# NBIOT.net
KiCad netlist of a schematic drawn in Altium Designer
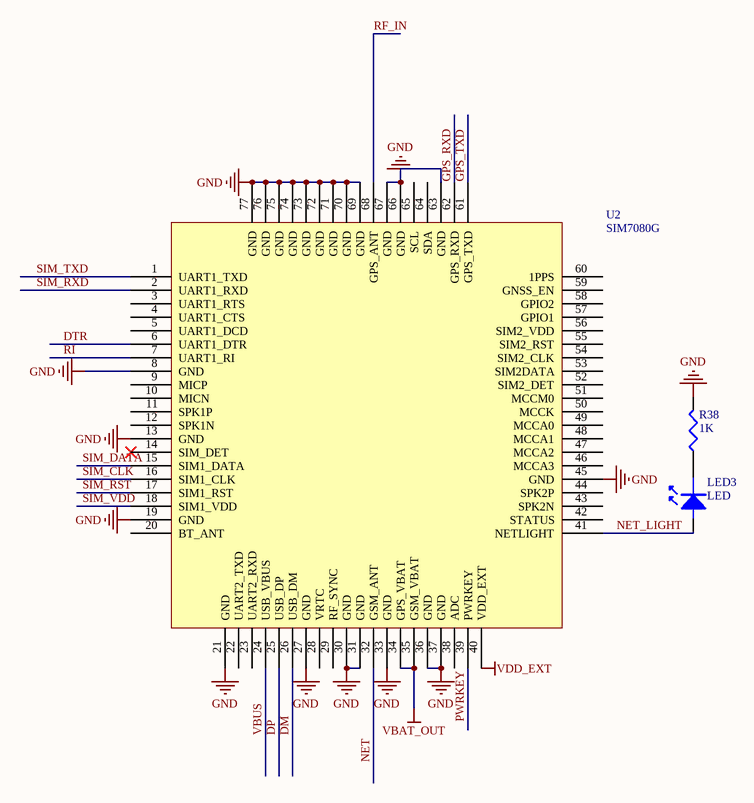
[diagram p0: NBIOT.SchDoc]

(export (version "E")
  (design (tool "Eeschema 10.0.6"))
  (components
    (comp (ref "LED3") (value "LED") (footprint "0603LED") (libsource (lib "我的元件库") (part "LED")))
    (comp (ref "R38")
      (value "1K")
      (footprint "0402R")
      (libsource (lib "ZWLIntegrated_Library") (part "RES1"))
    )
    (comp (ref "U2")
      (value "SIM7080G")
      (footprint "SIM868")
      (libsource (lib "stm32") (part "SIM868E/SIM868"))
    )
  )
  (nets
    (net (code "1") (name "/DM") (class "Default")
      (node (ref "U2") (pin "26") (pinfunction "USB_DM_26") (pintype "passive"))
    )
    (net (code "2") (name "/DP") (class "Default")
      (node (ref "U2") (pin "25") (pinfunction "USB_DP_25") (pintype "passive"))
    )
    (net (code "3") (name "/DTR") (class "Default")
      (node (ref "U2") (pin "6") (pinfunction "UART1_DTR_6") (pintype "passive"))
    )
    (net (code "4") (name "/GPS_RXD") (class "Default")
      (node (ref "U2") (pin "62") (pinfunction "GPS_RXD_62") (pintype "passive"))
    )
    (net (code "5") (name "/GPS_TXD") (class "Default")
      (node (ref "U2") (pin "61") (pinfunction "GPS_TXD_61") (pintype "passive"))
    )
    (net (code "6") (name "/NET") (class "Default")
      (node (ref "U2") (pin "32") (pinfunction "GSM_ANT_32") (pintype "passive"))
    )
    (net (code "7") (name "/NET_LIGHT") (class "Default")
      (node (ref "LED3") (pin "1") (pinfunction "1_1") (pintype "passive"))
      (node (ref "U2") (pin "41") (pinfunction "NETLIGHT_41") (pintype "passive"))
    )
    (net (code "8") (name "/PWRKEY") (class "Default")
      (node (ref "U2") (pin "39") (pinfunction "PWRKEY_39") (pintype "passive"))
    )
    (net (code "9") (name "/RF_IN") (class "Default")
      (node (ref "U2") (pin "68") (pinfunction "GPS_ANT_68") (pintype "passive"))
    )
    (net (code "10") (name "/RI") (class "Default")
      (node (ref "U2") (pin "7") (pinfunction "UART1_RI_7") (pintype "passive"))
    )
    (net (code "11") (name "/SIM_CLK") (class "Default")
      (node (ref "U2") (pin "16") (pinfunction "SIM1_CLK_16") (pintype "passive"))
    )
    (net (code "12") (name "/SIM_DATA") (class "Default")
      (node (ref "U2") (pin "15") (pinfunction "SIM1_DATA_15") (pintype "passive"))
    )
    (net (code "13") (name "/SIM_RST") (class "Default")
      (node (ref "U2") (pin "17") (pinfunction "SIM1_RST_17") (pintype "passive"))
    )
    (net (code "14") (name "/SIM_RXD") (class "Default")
      (node (ref "U2") (pin "2") (pinfunction "UART1_RXD_2") (pintype "passive"))
    )
    (net (code "15") (name "/SIM_TXD") (class "Default")
      (node (ref "U2") (pin "1") (pinfunction "UART1_TXD_1") (pintype "passive"))
    )
    (net (code "16") (name "/SIM_VDD") (class "Default")
      (node (ref "U2") (pin "18") (pinfunction "SIM1_VDD_18") (pintype "passive"))
    )
    (net (code "17") (name "/VBUS") (class "Default")
      (node (ref "U2") (pin "24") (pinfunction "USB_VBUS_24") (pintype "passive"))
    )
    (net (code "18") (name "GND") (class "Default")
      (node (ref "R38") (pin "2") (pinfunction "2_2") (pintype "passive"))
      (node (ref "U2") (pin "13") (pinfunction "GND_13") (pintype "passive"))
      (node (ref "U2") (pin "19") (pinfunction "GND_19") (pintype "passive"))
      (node (ref "U2") (pin "21") (pinfunction "GND_21") (pintype "passive"))
      (node (ref "U2") (pin "27") (pinfunction "GND_27") (pintype "passive"))
      (node (ref "U2") (pin "30") (pinfunction "GND_30") (pintype "passive"))
      (node (ref "U2") (pin "31") (pinfunction "GND_31") (pintype "passive"))
      (node (ref "U2") (pin "33") (pinfunction "GND_33") (pintype "passive"))
      (node (ref "U2") (pin "36") (pinfunction "GND_36") (pintype "passive"))
      (node (ref "U2") (pin "37") (pinfunction "GND_37") (pintype "passive"))
      (node (ref "U2") (pin "45") (pinfunction "GND_45") (pintype "passive"))
      (node (ref "U2") (pin "63") (pinfunction "GND_63") (pintype "passive"))
      (node (ref "U2") (pin "66") (pinfunction "GND_66") (pintype "passive"))
      (node (ref "U2") (pin "67") (pinfunction "GND_67") (pintype "passive"))
      (node (ref "U2") (pin "69") (pinfunction "GND_69") (pintype "passive"))
      (node (ref "U2") (pin "70") (pinfunction "GND_70") (pintype "passive"))
      (node (ref "U2") (pin "71") (pinfunction "GND_71") (pintype "passive"))
      (node (ref "U2") (pin "72") (pinfunction "GND_72") (pintype "passive"))
      (node (ref "U2") (pin "73") (pinfunction "GND_73") (pintype "passive"))
      (node (ref "U2") (pin "74") (pinfunction "GND_74") (pintype "passive"))
      (node (ref "U2") (pin "75") (pinfunction "GND_75") (pintype "passive"))
      (node (ref "U2") (pin "76") (pinfunction "GND_76") (pintype "passive"))
      (node (ref "U2") (pin "77") (pinfunction "GND_77") (pintype "passive"))
      (node (ref "U2") (pin "8") (pinfunction "GND_8") (pintype "passive"))
    )
    (net (code "19") (name "Net-(LED3-Pad2)") (class "Default")
      (node (ref "LED3") (pin "2") (pinfunction "2_2") (pintype "passive"))
      (node (ref "R38") (pin "1") (pinfunction "1_1") (pintype "passive"))
    )
    (net (code "20") (name "VBAT_OUT") (class "Default")
      (node (ref "U2") (pin "34") (pinfunction "GPS_VBAT_34") (pintype "passive"))
      (node (ref "U2") (pin "35") (pinfunction "GSM_VBAT_35") (pintype "passive"))
    )
    (net (code "21") (name "VDD_EXT") (class "Default")
      (node (ref "U2") (pin "40") (pinfunction "VDD_EXT_40") (pintype "passive"))
    )
    (net (code "22") (name "unconnected-(U2-1PPS-Pad60)") (class "Default")
      (node (ref "U2") (pin "60") (pinfunction "1PPS_60") (pintype "passive"))
    )
    (net (code "23") (name "unconnected-(U2-ADC-Pad38)") (class "Default")
      (node (ref "U2") (pin "38") (pinfunction "ADC_38") (pintype "passive"))
    )
    (net (code "24") (name "unconnected-(U2-BT_ANT-Pad20)") (class "Default")
      (node (ref "U2") (pin "20") (pinfunction "BT_ANT_20") (pintype "passive"))
    )
    (net (code "25") (name "unconnected-(U2-GNSS_EN-Pad59)") (class "Default")
      (node (ref "U2") (pin "59") (pinfunction "GNSS_EN_59") (pintype "passive"))
    )
    (net (code "26") (name "unconnected-(U2-GPIO1-Pad57)") (class "Default")
      (node (ref "U2") (pin "57") (pinfunction "GPIO1_57") (pintype "passive"))
    )
    (net (code "27") (name "unconnected-(U2-GPIO2-Pad58)") (class "Default")
      (node (ref "U2") (pin "58") (pinfunction "GPIO2_58") (pintype "passive"))
    )
    (net (code "28") (name "unconnected-(U2-MCCA0-Pad49)") (class "Default")
      (node (ref "U2") (pin "49") (pinfunction "MCCA0_49") (pintype "passive"))
    )
    (net (code "29") (name "unconnected-(U2-MCCA1-Pad48)") (class "Default")
      (node (ref "U2") (pin "48") (pinfunction "MCCA1_48") (pintype "passive"))
    )
    (net (code "30") (name "unconnected-(U2-MCCA2-Pad47)") (class "Default")
      (node (ref "U2") (pin "47") (pinfunction "MCCA2_47") (pintype "passive"))
    )
    (net (code "31") (name "unconnected-(U2-MCCA3-Pad46)") (class "Default")
      (node (ref "U2") (pin "46") (pinfunction "MCCA3_46") (pintype "passive"))
    )
    (net (code "32") (name "unconnected-(U2-MCCK-Pad50)") (class "Default")
      (node (ref "U2") (pin "50") (pinfunction "MCCK_50") (pintype "passive"))
    )
    (net (code "33") (name "unconnected-(U2-MCCM0-Pad51)") (class "Default")
      (node (ref "U2") (pin "51") (pinfunction "MCCM0_51") (pintype "passive"))
    )
    (net (code "34") (name "unconnected-(U2-MICN-Pad10)") (class "Default")
      (node (ref "U2") (pin "10") (pinfunction "MICN_10") (pintype "passive"))
    )
    (net (code "35") (name "unconnected-(U2-MICP-Pad9)") (class "Default")
      (node (ref "U2") (pin "9") (pinfunction "MICP_9") (pintype "passive"))
    )
    (net (code "36") (name "unconnected-(U2-RF_SYNC-Pad29)") (class "Default")
      (node (ref "U2") (pin "29") (pinfunction "RF_SYNC_29") (pintype "passive"))
    )
    (net (code "37") (name "unconnected-(U2-SCL-Pad65)") (class "Default")
      (node (ref "U2") (pin "65") (pinfunction "SCL_65") (pintype "passive"))
    )
    (net (code "38") (name "unconnected-(U2-SDA-Pad64)") (class "Default")
      (node (ref "U2") (pin "64") (pinfunction "SDA_64") (pintype "passive"))
    )
    (net (code "39") (name "unconnected-(U2-SIM2DATA-Pad53)") (class "Default")
      (node (ref "U2") (pin "53") (pinfunction "SIM2DATA_53") (pintype "passive"))
    )
    (net (code "40") (name "unconnected-(U2-SIM2_CLK-Pad54)") (class "Default")
      (node (ref "U2") (pin "54") (pinfunction "SIM2_CLK_54") (pintype "passive"))
    )
    (net (code "41") (name "unconnected-(U2-SIM2_DET-Pad52)") (class "Default")
      (node (ref "U2") (pin "52") (pinfunction "SIM2_DET_52") (pintype "passive"))
    )
    (net (code "42") (name "unconnected-(U2-SIM2_RST-Pad55)") (class "Default")
      (node (ref "U2") (pin "55") (pinfunction "SIM2_RST_55") (pintype "passive"))
    )
    (net (code "43") (name "unconnected-(U2-SIM2_VDD-Pad56)") (class "Default")
      (node (ref "U2") (pin "56") (pinfunction "SIM2_VDD_56") (pintype "passive"))
    )
    (net (code "44") (name "unconnected-(U2-SIM_DET-Pad14)") (class "Default")
      (node (ref "U2") (pin "14") (pinfunction "SIM_DET_14") (pintype "passive+no_connect"))
    )
    (net (code "45") (name "unconnected-(U2-SPK1N-Pad12)") (class "Default")
      (node (ref "U2") (pin "12") (pinfunction "SPK1N_12") (pintype "passive"))
    )
    (net (code "46") (name "unconnected-(U2-SPK1P-Pad11)") (class "Default")
      (node (ref "U2") (pin "11") (pinfunction "SPK1P_11") (pintype "passive"))
    )
    (net (code "47") (name "unconnected-(U2-SPK2N-Pad43)") (class "Default")
      (node (ref "U2") (pin "43") (pinfunction "SPK2N_43") (pintype "passive"))
    )
    (net (code "48") (name "unconnected-(U2-SPK2P-Pad44)") (class "Default")
      (node (ref "U2") (pin "44") (pinfunction "SPK2P_44") (pintype "passive"))
    )
    (net (code "49") (name "unconnected-(U2-STATUS-Pad42)") (class "Default")
      (node (ref "U2") (pin "42") (pinfunction "STATUS_42") (pintype "passive"))
    )
    (net (code "50") (name "unconnected-(U2-UART1_CTS-Pad4)") (class "Default")
      (node (ref "U2") (pin "4") (pinfunction "UART1_CTS_4") (pintype "passive"))
    )
    (net (code "51") (name "unconnected-(U2-UART1_DCD-Pad5)") (class "Default")
      (node (ref "U2") (pin "5") (pinfunction "UART1_DCD_5") (pintype "passive"))
    )
    (net (code "52") (name "unconnected-(U2-UART1_RTS-Pad3)") (class "Default")
      (node (ref "U2") (pin "3") (pinfunction "UART1_RTS_3") (pintype "passive"))
    )
    (net (code "53") (name "unconnected-(U2-UART2_RXD-Pad23)") (class "Default")
      (node (ref "U2") (pin "23") (pinfunction "UART2_RXD_23") (pintype "passive"))
    )
    (net (code "54") (name "unconnected-(U2-UART2_TXD-Pad22)") (class "Default")
      (node (ref "U2") (pin "22") (pinfunction "UART2_TXD_22") (pintype "passive"))
    )
    (net (code "55") (name "unconnected-(U2-VRTC-Pad28)") (class "Default")
      (node (ref "U2") (pin "28") (pinfunction "VRTC_28") (pintype "passive"))
    )
  )
)
